# VHF-Superregen-2-Transistor.net
KiCad netlist of a schematic drawn in EAGLE
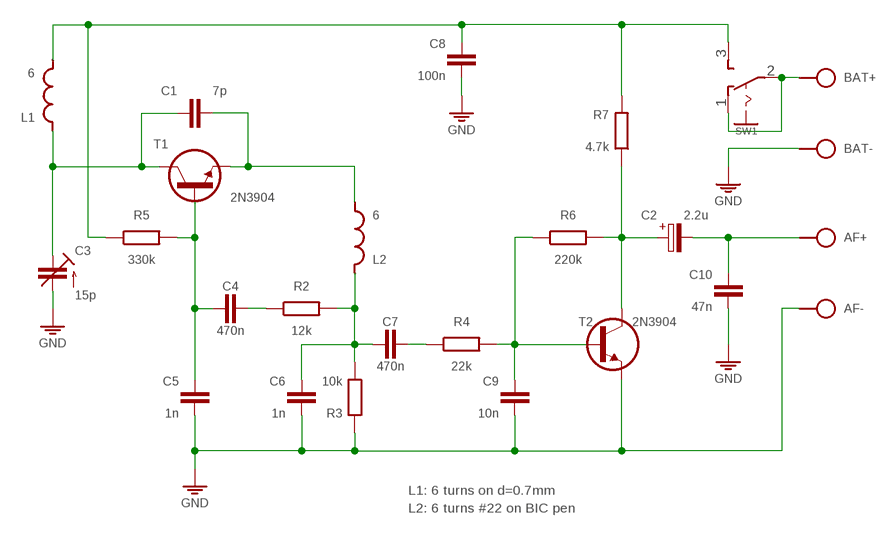
[diagram p0: schematic, sheet 1]

(export (version "E")
  (design (tool "Eeschema 10.0.6"))
  (components
    (comp (ref "AF+")
      (value "SPAD")
      (footprint "eagle-import:SPAD")
      (libsource (lib "eagle-import") (part "SPAD"))
    )
    (comp (ref "AF-")
      (value "SPAD")
      (footprint "eagle-import:SPAD")
      (libsource (lib "eagle-import") (part "SPAD"))
    )
    (comp (ref "BAT+")
      (value "SPAD")
      (footprint "eagle-import:SPAD")
      (libsource (lib "eagle-import") (part "SPAD"))
    )
    (comp (ref "BAT-")
      (value "SPAD")
      (footprint "eagle-import:SPAD")
      (libsource (lib "eagle-import") (part "SPAD"))
    )
    (comp (ref "C1")
      (value "7p")
      (footprint "eagle-import:C050-020X036")
      (libsource (lib "eagle-import") (part "C050-020X036"))
    )
    (comp (ref "C2")
      (value "2.2u")
      (footprint "eagle-import:E2,5-3")
      (libsource (lib "eagle-import") (part "CPOLE2,5-3"))
    )
    (comp (ref "C3")
      (value "15p")
      (footprint "eagle-import:TRIM-2222-808")
      (libsource (lib "eagle-import") (part "C-TR-PH201272222-808-2PIN"))
    )
    (comp (ref "C4")
      (value "470n")
      (footprint "eagle-import:C050-020X036")
      (libsource (lib "eagle-import") (part "C050-020X036"))
    )
    (comp (ref "C5")
      (value "1n")
      (footprint "eagle-import:C025-020X036")
      (libsource (lib "eagle-import") (part "C025-020X036"))
    )
    (comp (ref "C6")
      (value "1n")
      (footprint "eagle-import:C025-020X036")
      (libsource (lib "eagle-import") (part "C025-020X036"))
    )
    (comp (ref "C7")
      (value "470n")
      (footprint "eagle-import:C050-020X044")
      (libsource (lib "eagle-import") (part "C050-020X044"))
    )
    (comp (ref "C8")
      (value "100n")
      (footprint "eagle-import:C050-020X044_V")
      (libsource (lib "eagle-import") (part "C050-020X044/V"))
    )
    (comp (ref "C9")
      (value "10n")
      (footprint "eagle-import:C050-020X036_V")
      (libsource (lib "eagle-import") (part "C050-020X036/V"))
    )
    (comp (ref "C10")
      (value "47n")
      (footprint "eagle-import:C050-020X036")
      (libsource (lib "eagle-import") (part "C050-020X036"))
    )
    (comp (ref "L1")
      (value "6")
      (footprint "eagle-import:L-02_7V")
      (libsource (lib "eagle-import") (part "L-SHORT02/7V"))
    )
    (comp (ref "L2")
      (value "6")
      (footprint "eagle-import:L-02_5V")
      (libsource (lib "eagle-import") (part "L-SHORT02/5"))
    )
    (comp (ref "R2")
      (value "12k")
      (footprint "eagle-import:0202_7")
      (libsource (lib "eagle-import") (part "R0202/7"))
    )
    (comp (ref "R3")
      (value "10k")
      (footprint "eagle-import:0202_7")
      (libsource (lib "eagle-import") (part "R0202/7"))
    )
    (comp (ref "R4")
      (value "22k")
      (footprint "eagle-import:0202_7")
      (libsource (lib "eagle-import") (part "R0202/7"))
    )
    (comp (ref "R5")
      (value "330k")
      (footprint "eagle-import:0202_7-V")
      (libsource (lib "eagle-import") (part "R0202/7-V"))
    )
    (comp (ref "R6")
      (value "220k")
      (footprint "eagle-import:0202_7")
      (libsource (lib "eagle-import") (part "R0202/7"))
    )
    (comp (ref "R7")
      (value "4.7k")
      (footprint "eagle-import:0202_7-V")
      (libsource (lib "eagle-import") (part "R0202/7-V"))
    )
    (comp (ref "SW1")
      (value "SL-SW-1P-2T-H")
      (footprint "eagle-import:SLSW-1P2T-H")
      (libsource (lib "eagle-import") (part "SL-SW-1P-2T-H"))
    )
    (comp (ref "T1")
      (value "2N3904")
      (footprint "eagle-import:TO92")
      (libsource (lib "eagle-import") (part "2N3904"))
    )
    (comp (ref "T2")
      (value "2N3904")
      (footprint "eagle-import:TO92")
      (libsource (lib "eagle-import") (part "2N3904"))
    )
  )
  (nets
    (net (code "1") (name "GND") (class "Default")
      (node (ref "AF-") (pin "1") (pinfunction "P$1_1") (pintype "bidirectional"))
      (node (ref "BAT-") (pin "1") (pinfunction "P$1_1") (pintype "bidirectional"))
      (node (ref "C10") (pin "2") (pinfunction "2_2") (pintype "passive"))
      (node (ref "C3") (pin "2") (pinfunction "A_2") (pintype "passive"))
      (node (ref "C5") (pin "2") (pinfunction "2_2") (pintype "passive"))
      (node (ref "C6") (pin "2") (pinfunction "2_2") (pintype "passive"))
      (node (ref "C8") (pin "2") (pinfunction "2_2") (pintype "passive"))
      (node (ref "C9") (pin "2") (pinfunction "2_2") (pintype "passive"))
      (node (ref "R3") (pin "2") (pinfunction "2_2") (pintype "passive"))
      (node (ref "T2") (pin "1") (pinfunction "E_1") (pintype "passive"))
    )
    (net (code "2") (name "Net-(AF+-P$1)") (class "Default")
      (node (ref "AF+") (pin "1") (pinfunction "P$1_1") (pintype "bidirectional"))
      (node (ref "C10") (pin "1") (pinfunction "1_1") (pintype "passive"))
      (node (ref "C2") (pin "-") (pinfunction "-_-") (pintype "passive"))
    )
    (net (code "3") (name "Net-(BAT+-P$1)") (class "Default")
      (node (ref "BAT+") (pin "1") (pinfunction "P$1_1") (pintype "bidirectional"))
      (node (ref "SW1") (pin "1") (pinfunction "O_1") (pintype "passive"))
      (node (ref "SW1") (pin "2") (pinfunction "P_2") (pintype "passive"))
    )
    (net (code "4") (name "Net-(C3-E)") (class "Default")
      (node (ref "C1") (pin "2") (pinfunction "2_2") (pintype "passive"))
      (node (ref "C3") (pin "1") (pinfunction "E_1") (pintype "passive"))
      (node (ref "L1") (pin "1") (pinfunction "1_1") (pintype "passive"))
      (node (ref "T1") (pin "3") (pinfunction "C_3") (pintype "passive"))
    )
    (net (code "5") (name "Net-(C4-Pad1)") (class "Default")
      (node (ref "C4") (pin "1") (pinfunction "1_1") (pintype "passive"))
      (node (ref "R2") (pin "1") (pinfunction "1_1") (pintype "passive"))
    )
    (net (code "6") (name "Net-(C6-Pad1)") (class "Default")
      (node (ref "C6") (pin "1") (pinfunction "1_1") (pintype "passive"))
      (node (ref "C7") (pin "2") (pinfunction "2_2") (pintype "passive"))
      (node (ref "L2") (pin "1") (pinfunction "1_1") (pintype "passive"))
      (node (ref "R2") (pin "2") (pinfunction "2_2") (pintype "passive"))
      (node (ref "R3") (pin "1") (pinfunction "1_1") (pintype "passive"))
    )
    (net (code "7") (name "Net-(C7-Pad1)") (class "Default")
      (node (ref "C7") (pin "1") (pinfunction "1_1") (pintype "passive"))
      (node (ref "R4") (pin "1") (pinfunction "1_1") (pintype "passive"))
    )
    (net (code "8") (name "Net-(SW1-S)") (class "Default")
      (node (ref "C8") (pin "1") (pinfunction "1_1") (pintype "passive"))
      (node (ref "L1") (pin "2") (pinfunction "2_2") (pintype "passive"))
      (node (ref "R5") (pin "1") (pinfunction "1_1") (pintype "passive"))
      (node (ref "R7") (pin "2") (pinfunction "2_2") (pintype "passive"))
      (node (ref "SW1") (pin "3") (pinfunction "S_3") (pintype "passive"))
    )
    (net (code "9") (name "Net-(T1-B)") (class "Default")
      (node (ref "C4") (pin "2") (pinfunction "2_2") (pintype "passive"))
      (node (ref "C5") (pin "1") (pinfunction "1_1") (pintype "passive"))
      (node (ref "R5") (pin "2") (pinfunction "2_2") (pintype "passive"))
      (node (ref "T1") (pin "2") (pinfunction "B_2") (pintype "passive"))
    )
    (net (code "10") (name "Net-(T1-E)") (class "Default")
      (node (ref "C1") (pin "1") (pinfunction "1_1") (pintype "passive"))
      (node (ref "L2") (pin "2") (pinfunction "2_2") (pintype "passive"))
      (node (ref "T1") (pin "1") (pinfunction "E_1") (pintype "passive"))
    )
    (net (code "11") (name "Net-(T2-B)") (class "Default")
      (node (ref "C9") (pin "1") (pinfunction "1_1") (pintype "passive"))
      (node (ref "R4") (pin "2") (pinfunction "2_2") (pintype "passive"))
      (node (ref "R6") (pin "1") (pinfunction "1_1") (pintype "passive"))
      (node (ref "T2") (pin "2") (pinfunction "B_2") (pintype "passive"))
    )
    (net (code "12") (name "Net-(T2-C)") (class "Default")
      (node (ref "C2") (pin "+") (pinfunction "+_+") (pintype "passive"))
      (node (ref "R6") (pin "2") (pinfunction "2_2") (pintype "passive"))
      (node (ref "R7") (pin "1") (pinfunction "1_1") (pintype "passive"))
      (node (ref "T2") (pin "3") (pinfunction "C_3") (pintype "passive"))
    )
  )
)
